# stm32f446_core.net
KiCad netlist of a schematic drawn in Altium Designer
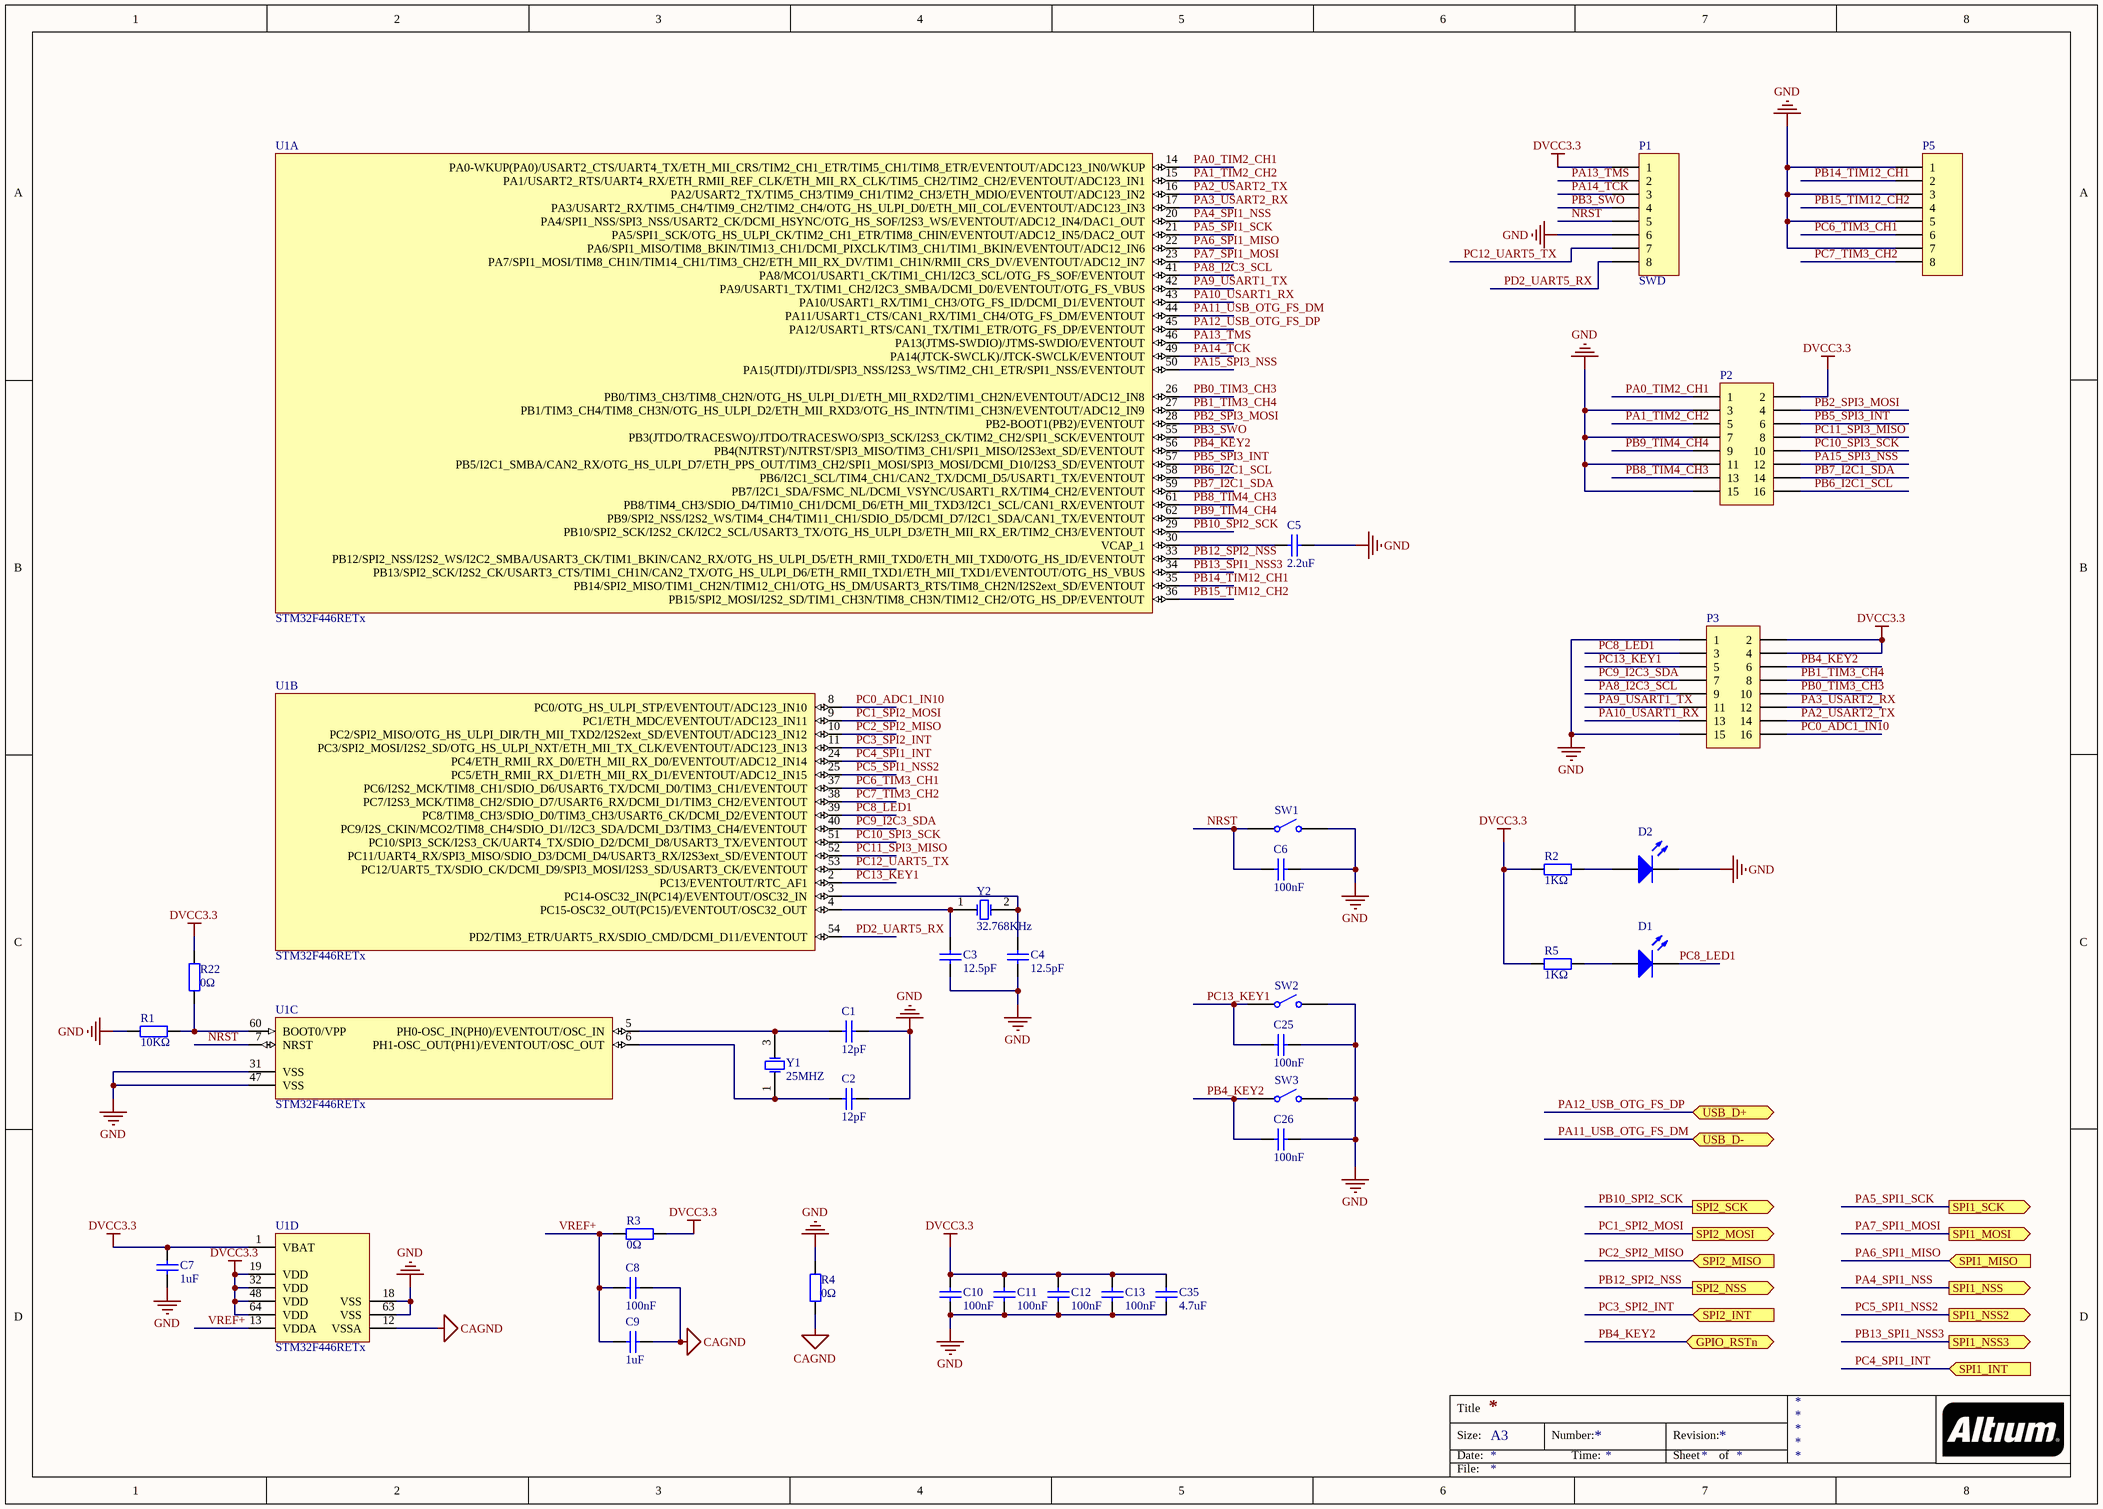
[diagram p0: stm32f446_core.SchDoc]

(export (version "E")
  (design (tool "Eeschema 10.0.6"))
  (components
    (comp (ref "C1")
      (value "12pF")
      (footprint "0603_C")
      (description "贴片电容")
      (libsource (lib "Miscellaneous Devices LC") (part "0603 12pF (120) 5% 50V"))
    )
    (comp (ref "C2")
      (value "12pF")
      (footprint "0603_C")
      (description "贴片电容")
      (libsource (lib "Miscellaneous Devices LC") (part "0603 12pF (120) 5% 50V"))
    )
    (comp (ref "C3")
      (value "12.5pF")
      (footprint "0603_C")
      (description "贴片电容")
      (libsource (lib "Miscellaneous Devices LC") (part "0603 12pF (120) 5% 50V"))
    )
    (comp (ref "C4")
      (value "12.5pF")
      (footprint "0603_C")
      (description "贴片电容")
      (libsource (lib "Miscellaneous Devices LC") (part "0603 12pF (120) 5% 50V"))
    )
    (comp (ref "C5")
      (value "2.2uF")
      (footprint "0603_C")
      (description "贴片电容")
      (libsource (lib "Miscellaneous Devices LC") (part "0603 2.2uF (225) 10% 16V"))
    )
    (comp (ref "C6")
      (value "100nF")
      (footprint "0603_C")
      (description "贴片电容")
      (libsource (lib "Miscellaneous Devices LC") (part "0603 100nF (104) 10% 50V"))
    )
    (comp (ref "C7")
      (value "1uF")
      (footprint "0603_C")
      (description "贴片电容")
      (libsource (lib "Miscellaneous Devices LC") (part "0603 1uF (105) 10% 50V"))
    )
    (comp (ref "C8")
      (value "100nF")
      (footprint "0603_C")
      (description "贴片电容")
      (libsource (lib "Miscellaneous Devices LC") (part "0603 100nF (104) 10% 50V"))
    )
    (comp (ref "C9")
      (value "1uF")
      (footprint "0603_C")
      (description "贴片电容")
      (libsource (lib "Miscellaneous Devices LC") (part "0603 1uF (105) 10% 50V"))
    )
    (comp (ref "C10")
      (value "100nF")
      (footprint "0603_C")
      (description "贴片电容")
      (libsource (lib "Miscellaneous Devices LC") (part "0603 100nF (104) 10% 50V"))
    )
    (comp (ref "C11")
      (value "100nF")
      (footprint "0603_C")
      (description "贴片电容")
      (libsource (lib "Miscellaneous Devices LC") (part "0603 100nF (104) 10% 50V"))
    )
    (comp (ref "C12")
      (value "100nF")
      (footprint "0603_C")
      (description "贴片电容")
      (libsource (lib "Miscellaneous Devices LC") (part "0603 100nF (104) 10% 50V"))
    )
    (comp (ref "C13")
      (value "100nF")
      (footprint "0603_C")
      (description "贴片电容")
      (libsource (lib "Miscellaneous Devices LC") (part "0603 100nF (104) 10% 50V"))
    )
    (comp (ref "C25")
      (value "100nF")
      (footprint "0603_C")
      (description "贴片电容")
      (libsource (lib "Miscellaneous Devices LC") (part "0603 100nF (104) 10% 50V"))
    )
    (comp (ref "C26")
      (value "100nF")
      (footprint "0603_C")
      (description "贴片电容")
      (libsource (lib "Miscellaneous Devices LC") (part "0603 100nF (104) 10% 50V"))
    )
    (comp (ref "C35")
      (value "4.7uF")
      (footprint "0603_C")
      (description "贴片电容")
      (libsource (lib "Miscellaneous Devices LC") (part "0603 4.7uF (475) 10% 16V"))
    )
    (comp (ref "D1")
      (value "蓝灯 0805")
      (footprint "0805_LED_S1")
      (description "发光二极管")
      (libsource (lib "Miscellaneous Devices LC") (part "0805 蓝灯"))
    )
    (comp (ref "D2")
      (value "蓝灯 0805")
      (footprint "0805_LED_S1")
      (description "发光二极管")
      (libsource (lib "Miscellaneous Devices LC") (part "0805 蓝灯"))
    )
    (comp (ref "P1")
      (value "SWD")
      (footprint "HDR1X8")
      (description "Header, 8-Pin")
      (fields (field (name "PUBLISHER") "Altium Limited"))
      (libsource (lib "Miscellaneous Connectors") (part "Header 8"))
    )
    (comp (ref "P2")
      (value "Header 8X2")
      (footprint "HDR2X8")
      (description "Header, 8-Pin, Dual row")
      (fields (field (name "PUBLISHER") "Altium Limited"))
      (libsource (lib "Miscellaneous Connectors") (part "Header 8X2"))
    )
    (comp (ref "P3")
      (value "Header 8X2")
      (footprint "HDR2X8")
      (description "Header, 8-Pin, Dual row")
      (fields (field (name "PUBLISHER") "Altium Limited"))
      (libsource (lib "Miscellaneous Connectors") (part "Header 8X2"))
    )
    (comp (ref "P5")
      (value "Header 8")
      (footprint "HDR1X8")
      (description "Header, 8-Pin")
      (fields (field (name "PUBLISHER") "Altium Limited"))
      (libsource (lib "Miscellaneous Connectors") (part "Header 8"))
    )
    (comp (ref "R1")
      (value "10KΩ")
      (footprint "0603_R")
      (description "贴片电阻")
      (libsource (lib "Miscellaneous Devices LC") (part "0603 10KΩ (1002) 1%"))
    )
    (comp (ref "R2")
      (value "1KΩ")
      (footprint "0603_R")
      (description "贴片电阻")
      (libsource (lib "Miscellaneous Devices LC") (part "0603 1KΩ (1001) 1%"))
    )
    (comp (ref "R3")
      (value "0Ω")
      (footprint "0603_R")
      (description "贴片电阻")
      (libsource (lib "") (part "0603 0Ω (0R0) 1%_1"))
    )
    (comp (ref "R4")
      (value "0Ω")
      (footprint "0603_R")
      (description "贴片电阻")
      (libsource (lib "Miscellaneous Devices LC") (part "0603 0Ω (0R0) 1%"))
    )
    (comp (ref "R5")
      (value "1KΩ")
      (footprint "0603_R")
      (description "贴片电阻")
      (libsource (lib "Miscellaneous Devices LC") (part "0603 1KΩ (1001) 1%"))
    )
    (comp (ref "R22")
      (value "0Ω")
      (footprint "0603_R")
      (description "贴片电阻")
      (libsource (lib "Miscellaneous Devices LC") (part "0603 0Ω (0R0) 1%"))
    )
    (comp (ref "SW1")
      (value "434111025826")
      (footprint "434111025826")
      (description "WS-TASV SMD Tact Switch 6.0X3.8 mm")
      (libsource (lib "WS-TASV SMD Tact Switch 6.0X3.5 mm") (part "434111025826"))
    )
    (comp (ref "SW2")
      (value "434111025826")
      (footprint "434111025826")
      (description "WS-TASV SMD Tact Switch 6.0X3.8 mm")
      (libsource (lib "WS-TASV SMD Tact Switch 6.0X3.5 mm") (part "434111025826"))
    )
    (comp (ref "SW3")
      (value "434111025826")
      (footprint "434111025826")
      (description "WS-TASV SMD Tact Switch 6.0X3.8 mm")
      (libsource (lib "WS-TASV SMD Tact Switch 6.0X3.5 mm") (part "434111025826"))
    )
    (comp (ref "U1")
      (value "STM32F446RETx")
      (footprint "LQFP-64_10x10x05P")
      (description "ARM")
      (libsource (lib "Miscellaneous Devices LC") (part "STM32F405RGT6"))
    )
    (comp (ref "Y1")
      (value "25MHZ")
      (footprint "SMD-3225_4P")
      (description "贴片晶振")
      (libsource (lib "Miscellaneous Devices LC") (part "SMD-3225_4P  25MHZ 12PF 10PPM"))
    )
    (comp (ref "Y2")
      (value "32.768KHz")
      (footprint "SMD-3215_2P FC - 135")
      (description "贴片晶振")
      (libsource (lib "Miscellaneous Devices LC") (part "SMD-3215_2P 32.768KHz 20ppm 12.5pF"))
    )
  )
  (nets
    (net (code "1") (name "/NRST") (class "Default")
      (node (ref "C6") (pin "1") (pinfunction "1_1") (pintype "passive"))
      (node (ref "P1") (pin "5") (pinfunction "5_5") (pintype "passive"))
      (node (ref "SW1") (pin "1") (pinfunction "1_1") (pintype "passive"))
      (node (ref "U1") (pin "7") (pinfunction "NRST_7") (pintype "bidirectional"))
    )
    (net (code "2") (name "/PA0_TIM2_CH1") (class "Default")
      (node (ref "P2") (pin "1") (pinfunction "1_1") (pintype "passive"))
      (node (ref "U1") (pin "14") (pinfunction "PA0-WKUP(PA0)/USART2_CTS/UART4_TX/ETH_MII_CRS/TIM2_CH1_ETR/TIM5_CH1/TIM8_ETR/EVENTOUT/ADC123_IN0/WKUP_14") (pintype "bidirectional"))
    )
    (net (code "3") (name "/PA1_TIM2_CH2") (class "Default")
      (node (ref "P2") (pin "5") (pinfunction "5_5") (pintype "passive"))
      (node (ref "U1") (pin "15") (pinfunction "PA1/USART2_RTS/UART4_RX/ETH_RMII_REF_CLK/ETH_MII_RX_CLK/TIM5_CH2/TIM2_CH2/EVENTOUT/ADC123_IN1_15") (pintype "bidirectional"))
    )
    (net (code "4") (name "/PA2_USART2_TX") (class "Default")
      (node (ref "P3") (pin "14") (pinfunction "14_14") (pintype "passive"))
      (node (ref "U1") (pin "16") (pinfunction "PA2/USART2_TX/TIM5_CH3/TIM9_CH1/TIM2_CH3/ETH_MDIO/EVENTOUT/ADC123_IN2_16") (pintype "bidirectional"))
    )
    (net (code "5") (name "/PA3_USART2_RX") (class "Default")
      (node (ref "P3") (pin "12") (pinfunction "12_12") (pintype "passive"))
      (node (ref "U1") (pin "17") (pinfunction "PA3/USART2_RX/TIM5_CH4/TIM9_CH2/TIM2_CH4/OTG_HS_ULPI_D0/ETH_MII_COL/EVENTOUT/ADC123_IN3_17") (pintype "bidirectional"))
    )
    (net (code "6") (name "/PA4_SPI1_NSS") (class "Default")
      (node (ref "U1") (pin "20") (pinfunction "PA4/SPI1_NSS/SPI3_NSS/USART2_CK/DCMI_HSYNC/OTG_HS_SOF/I2S3_WS/EVENTOUT/ADC12_IN4/DAC1_OUT_20") (pintype "bidirectional"))
    )
    (net (code "7") (name "/PA5_SPI1_SCK") (class "Default")
      (node (ref "U1") (pin "21") (pinfunction "PA5/SPI1_SCK/OTG_HS_ULPI_CK/TIM2_CH1_ETR/TIM8_CHIN/EVENTOUT/ADC12_IN5/DAC2_OUT_21") (pintype "bidirectional"))
    )
    (net (code "8") (name "/PA6_SPI1_MISO") (class "Default")
      (node (ref "U1") (pin "22") (pinfunction "PA6/SPI1_MISO/TIM8_BKIN/TIM13_CH1/DCMI_PIXCLK/TIM3_CH1/TIM1_BKIN/EVENTOUT/ADC12_IN6_22") (pintype "bidirectional"))
    )
    (net (code "9") (name "/PA7_SPI1_MOSI") (class "Default")
      (node (ref "U1") (pin "23") (pinfunction "PA7/SPI1_MOSI/TIM8_CH1N/TIM14_CH1/TIM3_CH2/ETH_MII_RX_DV/TIM1_CH1N/RMII_CRS_DV/EVENTOUT/ADC12_IN7_23") (pintype "bidirectional"))
    )
    (net (code "10") (name "/PA8_I2C3_SCL") (class "Default")
      (node (ref "P3") (pin "9") (pinfunction "9_9") (pintype "passive"))
      (node (ref "U1") (pin "41") (pinfunction "PA8/MCO1/USART1_CK/TIM1_CH1/I2C3_SCL/OTG_FS_SOF/EVENTOUT_41") (pintype "bidirectional"))
    )
    (net (code "11") (name "/PA9_USART1_TX") (class "Default")
      (node (ref "P3") (pin "11") (pinfunction "11_11") (pintype "passive"))
      (node (ref "U1") (pin "42") (pinfunction "PA9/USART1_TX/TIM1_CH2/I2C3_SMBA/DCMI_D0/EVENTOUT/OTG_FS_VBUS_42") (pintype "bidirectional"))
    )
    (net (code "12") (name "/PA10_USART1_RX") (class "Default")
      (node (ref "P3") (pin "13") (pinfunction "13_13") (pintype "passive"))
      (node (ref "U1") (pin "43") (pinfunction "PA10/USART1_RX/TIM1_CH3/OTG_FS_ID/DCMI_D1/EVENTOUT_43") (pintype "bidirectional"))
    )
    (net (code "13") (name "/PA11_USB_OTG_FS_DM") (class "Default")
      (node (ref "U1") (pin "44") (pinfunction "PA11/USART1_CTS/CAN1_RX/TIM1_CH4/OTG_FS_DM/EVENTOUT_44") (pintype "bidirectional"))
    )
    (net (code "14") (name "/PA12_USB_OTG_FS_DP") (class "Default")
      (node (ref "U1") (pin "45") (pinfunction "PA12/USART1_RTS/CAN1_TX/TIM1_ETR/OTG_FS_DP/EVENTOUT_45") (pintype "bidirectional"))
    )
    (net (code "15") (name "/PA13_TMS") (class "Default")
      (node (ref "P1") (pin "2") (pinfunction "2_2") (pintype "passive"))
      (node (ref "U1") (pin "46") (pinfunction "PA13(JTMS-SWDIO)/JTMS-SWDIO/EVENTOUT_46") (pintype "bidirectional"))
    )
    (net (code "16") (name "/PA14_TCK") (class "Default")
      (node (ref "P1") (pin "3") (pinfunction "3_3") (pintype "passive"))
      (node (ref "U1") (pin "49") (pinfunction "PA14(JTCK-SWCLK)/JTCK-SWCLK/EVENTOUT_49") (pintype "bidirectional"))
    )
    (net (code "17") (name "/PA15_SPI3_NSS") (class "Default")
      (node (ref "P2") (pin "12") (pinfunction "12_12") (pintype "passive"))
      (node (ref "U1") (pin "50") (pinfunction "PA15(JTDI)/JTDI/SPI3_NSS/I2S3_WS/TIM2_CH1_ETR/SPI1_NSS/EVENTOUT_50") (pintype "bidirectional"))
    )
    (net (code "18") (name "/PB0_TIM3_CH3") (class "Default")
      (node (ref "P3") (pin "10") (pinfunction "10_10") (pintype "passive"))
      (node (ref "U1") (pin "26") (pinfunction "PB0/TIM3_CH3/TIM8_CH2N/OTG_HS_ULPI_D1/ETH_MII_RXD2/TIM1_CH2N/EVENTOUT/ADC12_IN8_26") (pintype "bidirectional"))
    )
    (net (code "19") (name "/PB1_TIM3_CH4") (class "Default")
      (node (ref "P3") (pin "8") (pinfunction "8_8") (pintype "passive"))
      (node (ref "U1") (pin "27") (pinfunction "PB1/TIM3_CH4/TIM8_CH3N/OTG_HS_ULPI_D2/ETH_MII_RXD3/OTG_HS_INTN/TIM1_CH3N/EVENTOUT/ADC12_IN9_27") (pintype "bidirectional"))
    )
    (net (code "20") (name "/PB2_SPI3_MOSI") (class "Default")
      (node (ref "P2") (pin "4") (pinfunction "4_4") (pintype "passive"))
      (node (ref "U1") (pin "28") (pinfunction "PB2-BOOT1(PB2)/EVENTOUT_28") (pintype "bidirectional"))
    )
    (net (code "21") (name "/PB3_SWO") (class "Default")
      (node (ref "P1") (pin "4") (pinfunction "4_4") (pintype "passive"))
      (node (ref "U1") (pin "55") (pinfunction "PB3(JTDO/TRACESWO)/JTDO/TRACESWO/SPI3_SCK/I2S3_CK/TIM2_CH2/SPI1_SCK/EVENTOUT_55") (pintype "bidirectional"))
    )
    (net (code "22") (name "/PB4_KEY2") (class "Default")
      (node (ref "C26") (pin "1") (pinfunction "1_1") (pintype "passive"))
      (node (ref "P3") (pin "6") (pinfunction "6_6") (pintype "passive"))
      (node (ref "SW3") (pin "1") (pinfunction "1_1") (pintype "passive"))
      (node (ref "U1") (pin "56") (pinfunction "PB4(NJTRST)/NJTRST/SPI3_MISO/TIM3_CH1/SPI1_MISO/I2S3ext_SD/EVENTOUT_56") (pintype "bidirectional"))
    )
    (net (code "23") (name "/PB5_SPI3_INT") (class "Default")
      (node (ref "P2") (pin "6") (pinfunction "6_6") (pintype "passive"))
      (node (ref "U1") (pin "57") (pinfunction "PB5/I2C1_SMBA/CAN2_RX/OTG_HS_ULPI_D7/ETH_PPS_OUT/TIM3_CH2/SPI1_MOSI/SPI3_MOSI/DCMI_D10/I2S3_SD/EVENTOUT_57") (pintype "bidirectional"))
    )
    (net (code "24") (name "/PB6_I2C1_SCL") (class "Default")
      (node (ref "P2") (pin "16") (pinfunction "16_16") (pintype "passive"))
      (node (ref "U1") (pin "58") (pinfunction "PB6/I2C1_SCL/TIM4_CH1/CAN2_TX/DCMI_D5/USART1_TX/EVENTOUT_58") (pintype "bidirectional"))
    )
    (net (code "25") (name "/PB7_I2C1_SDA") (class "Default")
      (node (ref "P2") (pin "14") (pinfunction "14_14") (pintype "passive"))
      (node (ref "U1") (pin "59") (pinfunction "PB7/I2C1_SDA/FSMC_NL/DCMI_VSYNC/USART1_RX/TIM4_CH2/EVENTOUT_59") (pintype "bidirectional"))
    )
    (net (code "26") (name "/PB8_TIM4_CH3") (class "Default")
      (node (ref "P2") (pin "13") (pinfunction "13_13") (pintype "passive"))
      (node (ref "U1") (pin "61") (pinfunction "PB8/TIM4_CH3/SDIO_D4/TIM10_CH1/DCMI_D6/ETH_MII_TXD3/I2C1_SCL/CAN1_RX/EVENTOUT_61") (pintype "bidirectional"))
    )
    (net (code "27") (name "/PB9_TIM4_CH4") (class "Default")
      (node (ref "P2") (pin "9") (pinfunction "9_9") (pintype "passive"))
      (node (ref "U1") (pin "62") (pinfunction "PB9/SPI2_NSS/I2S2_WS/TIM4_CH4/TIM11_CH1/SDIO_D5/DCMI_D7/I2C1_SDA/CAN1_TX/EVENTOUT_62") (pintype "bidirectional"))
    )
    (net (code "28") (name "/PB10_SPI2_SCK") (class "Default")
      (node (ref "U1") (pin "29") (pinfunction "PB10/SPI2_SCK/I2S2_CK/I2C2_SCL/USART3_TX/OTG_HS_ULPI_D3/ETH_MII_RX_ER/TIM2_CH3/EVENTOUT_29") (pintype "bidirectional"))
    )
    (net (code "29") (name "/PB12_SPI2_NSS") (class "Default")
      (node (ref "U1") (pin "33") (pinfunction "PB12/SPI2_NSS/I2S2_WS/I2C2_SMBA/USART3_CK/TIM1_BKIN/CAN2_RX/OTG_HS_ULPI_D5/ETH_RMII_TXD0/ETH_MII_TXD0/OTG_HS_ID/EVENTOUT_33") (pintype "bidirectional"))
    )
    (net (code "30") (name "/PB13_SPI1_NSS3") (class "Default")
      (node (ref "U1") (pin "34") (pinfunction "PB13/SPI2_SCK/I2S2_CK/USART3_CTS/TIM1_CH1N/CAN2_TX/OTG_HS_ULPI_D6/ETH_RMII_TXD1/ETH_MII_TXD1/EVENTOUT/OTG_HS_VBUS_34") (pintype "bidirectional"))
    )
    (net (code "31") (name "/PB14_TIM12_CH1") (class "Default")
      (node (ref "P5") (pin "2") (pinfunction "2_2") (pintype "passive"))
      (node (ref "U1") (pin "35") (pinfunction "PB14/SPI2_MISO/TIM1_CH2N/TIM12_CH1/OTG_HS_DM/USART3_RTS/TIM8_CH2N/I2S2ext_SD/EVENTOUT_35") (pintype "bidirectional"))
    )
    (net (code "32") (name "/PB15_TIM12_CH2") (class "Default")
      (node (ref "P5") (pin "4") (pinfunction "4_4") (pintype "passive"))
      (node (ref "U1") (pin "36") (pinfunction "PB15/SPI2_MOSI/I2S2_SD/TIM1_CH3N/TIM8_CH3N/TIM12_CH2/OTG_HS_DP/EVENTOUT_36") (pintype "bidirectional"))
    )
    (net (code "33") (name "/PC0_ADC1_IN10") (class "Default")
      (node (ref "P3") (pin "16") (pinfunction "16_16") (pintype "passive"))
      (node (ref "U1") (pin "8") (pinfunction "PC0/OTG_HS_ULPI_STP/EVENTOUT/ADC123_IN10_8") (pintype "bidirectional"))
    )
    (net (code "34") (name "/PC1_SPI2_MOSI") (class "Default")
      (node (ref "U1") (pin "9") (pinfunction "PC1/ETH_MDC/EVENTOUT/ADC123_IN11_9") (pintype "bidirectional"))
    )
    (net (code "35") (name "/PC2_SPI2_MISO") (class "Default")
      (node (ref "U1") (pin "10") (pinfunction "PC2/SPI2_MISO/OTG_HS_ULPI_DIR/TH_MII_TXD2/I2S2ext_SD/EVENTOUT/ADC123_IN12_10") (pintype "bidirectional"))
    )
    (net (code "36") (name "/PC3_SPI2_INT") (class "Default")
      (node (ref "U1") (pin "11") (pinfunction "PC3/SPI2_MOSI/I2S2_SD/OTG_HS_ULPI_NXT/ETH_MII_TX_CLK/EVENTOUT/ADC123_IN13_11") (pintype "bidirectional"))
    )
    (net (code "37") (name "/PC4_SPI1_INT") (class "Default")
      (node (ref "U1") (pin "24") (pinfunction "PC4/ETH_RMII_RX_D0/ETH_MII_RX_D0/EVENTOUT/ADC12_IN14_24") (pintype "bidirectional"))
    )
    (net (code "38") (name "/PC5_SPI1_NSS2") (class "Default")
      (node (ref "U1") (pin "25") (pinfunction "PC5/ETH_RMII_RX_D1/ETH_MII_RX_D1/EVENTOUT/ADC12_IN15_25") (pintype "bidirectional"))
    )
    (net (code "39") (name "/PC6_TIM3_CH1") (class "Default")
      (node (ref "P5") (pin "6") (pinfunction "6_6") (pintype "passive"))
      (node (ref "U1") (pin "37") (pinfunction "PC6/I2S2_MCK/TIM8_CH1/SDIO_D6/USART6_TX/DCMI_D0/TIM3_CH1/EVENTOUT_37") (pintype "bidirectional"))
    )
    (net (code "40") (name "/PC7_TIM3_CH2") (class "Default")
      (node (ref "P5") (pin "8") (pinfunction "8_8") (pintype "passive"))
      (node (ref "U1") (pin "38") (pinfunction "PC7/I2S3_MCK/TIM8_CH2/SDIO_D7/USART6_RX/DCMI_D1/TIM3_CH2/EVENTOUT_38") (pintype "bidirectional"))
    )
    (net (code "41") (name "/PC8_LED1") (class "Default")
      (node (ref "D1") (pin "K") (pinfunction "K_K") (pintype "passive"))
      (node (ref "P3") (pin "3") (pinfunction "3_3") (pintype "passive"))
      (node (ref "U1") (pin "39") (pinfunction "PC8/TIM8_CH3/SDIO_D0/TIM3_CH3/USART6_CK/DCMI_D2/EVENTOUT_39") (pintype "bidirectional"))
    )
    (net (code "42") (name "/PC9_I2C3_SDA") (class "Default")
      (node (ref "P3") (pin "7") (pinfunction "7_7") (pintype "passive"))
      (node (ref "U1") (pin "40") (pinfunction "PC9/I2S_CKIN/MCO2/TIM8_CH4/SDIO_D1//I2C3_SDA/DCMI_D3/TIM3_CH4/EVENTOUT_40") (pintype "bidirectional"))
    )
    (net (code "43") (name "/PC10_SPI3_SCK") (class "Default")
      (node (ref "P2") (pin "10") (pinfunction "10_10") (pintype "passive"))
      (node (ref "U1") (pin "51") (pinfunction "PC10/SPI3_SCK/I2S3_CK/UART4_TX/SDIO_D2/DCMI_D8/USART3_TX/EVENTOUT_51") (pintype "bidirectional"))
    )
    (net (code "44") (name "/PC11_SPI3_MISO") (class "Default")
      (node (ref "P2") (pin "8") (pinfunction "8_8") (pintype "passive"))
      (node (ref "U1") (pin "52") (pinfunction "PC11/UART4_RX/SPI3_MISO/SDIO_D3/DCMI_D4/USART3_RX/I2S3ext_SD/EVENTOUT_52") (pintype "bidirectional"))
    )
    (net (code "45") (name "/PC12_UART5_TX") (class "Default")
      (node (ref "P1") (pin "7") (pinfunction "7_7") (pintype "passive"))
      (node (ref "U1") (pin "53") (pinfunction "PC12/UART5_TX/SDIO_CK/DCMI_D9/SPI3_MOSI/I2S3_SD/USART3_CK/EVENTOUT_53") (pintype "bidirectional"))
    )
    (net (code "46") (name "/PC13_KEY1") (class "Default")
      (node (ref "C25") (pin "1") (pinfunction "1_1") (pintype "passive"))
      (node (ref "P3") (pin "5") (pinfunction "5_5") (pintype "passive"))
      (node (ref "SW2") (pin "1") (pinfunction "1_1") (pintype "passive"))
      (node (ref "U1") (pin "2") (pinfunction "PC13/EVENTOUT/RTC_AF1_2") (pintype "bidirectional"))
    )
    (net (code "47") (name "/PD2_UART5_RX") (class "Default")
      (node (ref "P1") (pin "8") (pinfunction "8_8") (pintype "passive"))
      (node (ref "U1") (pin "54") (pinfunction "PD2/TIM3_ETR/UART5_RX/SDIO_CMD/DCMI_D11/EVENTOUT_54") (pintype "bidirectional"))
    )
    (net (code "48") (name "/VREF+") (class "Default")
      (node (ref "C8") (pin "1") (pinfunction "1_1") (pintype "passive"))
      (node (ref "C9") (pin "1") (pinfunction "1_1") (pintype "passive"))
      (node (ref "R3") (pin "1") (pinfunction "1_1") (pintype "passive"))
      (node (ref "U1") (pin "13") (pinfunction "VDDA_13") (pintype "power_in"))
    )
    (net (code "49") (name "CAGND") (class "Default")
      (node (ref "C8") (pin "2") (pinfunction "2_2") (pintype "passive"))
      (node (ref "C9") (pin "2") (pinfunction "2_2") (pintype "passive"))
      (node (ref "R4") (pin "1") (pinfunction "1_1") (pintype "passive"))
      (node (ref "U1") (pin "12") (pinfunction "VSSA_12") (pintype "power_in"))
    )
    (net (code "50") (name "DVCC3.3") (class "Default")
      (node (ref "C10") (pin "2") (pinfunction "2_2") (pintype "passive"))
      (node (ref "C11") (pin "2") (pinfunction "2_2") (pintype "passive"))
      (node (ref "C12") (pin "2") (pinfunction "2_2") (pintype "passive"))
      (node (ref "C13") (pin "1") (pinfunction "1_1") (pintype "passive"))
      (node (ref "C35") (pin "2") (pinfunction "2_2") (pintype "passive"))
      (node (ref "C7") (pin "2") (pinfunction "2_2") (pintype "passive"))
      (node (ref "P1") (pin "1") (pinfunction "1_1") (pintype "passive"))
      (node (ref "P2") (pin "2") (pinfunction "2_2") (pintype "passive"))
      (node (ref "P3") (pin "2") (pinfunction "2_2") (pintype "passive"))
      (node (ref "P3") (pin "4") (pinfunction "4_4") (pintype "passive"))
      (node (ref "R2") (pin "1") (pinfunction "1_1") (pintype "passive"))
      (node (ref "R22") (pin "2") (pinfunction "2_2") (pintype "passive"))
      (node (ref "R3") (pin "2") (pinfunction "2_2") (pintype "passive"))
      (node (ref "R5") (pin "1") (pinfunction "1_1") (pintype "passive"))
      (node (ref "U1") (pin "1") (pinfunction "VBAT_1") (pintype "power_in"))
      (node (ref "U1") (pin "19") (pinfunction "VDD_19") (pintype "power_in"))
      (node (ref "U1") (pin "32") (pinfunction "VDD_32") (pintype "power_in"))
      (node (ref "U1") (pin "48") (pinfunction "VDD_48") (pintype "power_in"))
      (node (ref "U1") (pin "64") (pinfunction "VDD_64") (pintype "power_in"))
    )
    (net (code "51") (name "GND") (class "Default")
      (node (ref "C1") (pin "2") (pinfunction "2_2") (pintype "passive"))
      (node (ref "C10") (pin "1") (pinfunction "1_1") (pintype "passive"))
      (node (ref "C11") (pin "1") (pinfunction "1_1") (pintype "passive"))
      (node (ref "C12") (pin "1") (pinfunction "1_1") (pintype "passive"))
      (node (ref "C13") (pin "2") (pinfunction "2_2") (pintype "passive"))
      (node (ref "C2") (pin "2") (pinfunction "2_2") (pintype "passive"))
      (node (ref "C25") (pin "2") (pinfunction "2_2") (pintype "passive"))
      (node (ref "C26") (pin "2") (pinfunction "2_2") (pintype "passive"))
      (node (ref "C3") (pin "1") (pinfunction "1_1") (pintype "passive"))
      (node (ref "C35") (pin "1") (pinfunction "1_1") (pintype "passive"))
      (node (ref "C4") (pin "1") (pinfunction "1_1") (pintype "passive"))
      (node (ref "C5") (pin "1") (pinfunction "1_1") (pintype "passive"))
      (node (ref "C6") (pin "2") (pinfunction "2_2") (pintype "passive"))
      (node (ref "C7") (pin "1") (pinfunction "1_1") (pintype "passive"))
      (node (ref "D2") (pin "K") (pinfunction "K_K") (pintype "passive"))
      (node (ref "P1") (pin "6") (pinfunction "6_6") (pintype "passive"))
      (node (ref "P2") (pin "11") (pinfunction "11_11") (pintype "passive"))
      (node (ref "P2") (pin "15") (pinfunction "15_15") (pintype "passive"))
      (node (ref "P2") (pin "3") (pinfunction "3_3") (pintype "passive"))
      (node (ref "P2") (pin "7") (pinfunction "7_7") (pintype "passive"))
      (node (ref "P3") (pin "1") (pinfunction "1_1") (pintype "passive"))
      (node (ref "P3") (pin "15") (pinfunction "15_15") (pintype "passive"))
      (node (ref "P5") (pin "1") (pinfunction "1_1") (pintype "passive"))
      (node (ref "P5") (pin "3") (pinfunction "3_3") (pintype "passive"))
      (node (ref "P5") (pin "5") (pinfunction "5_5") (pintype "passive"))
      (node (ref "P5") (pin "7") (pinfunction "7_7") (pintype "passive"))
      (node (ref "R1") (pin "1") (pinfunction "1_1") (pintype "passive"))
      (node (ref "R4") (pin "2") (pinfunction "2_2") (pintype "passive"))
      (node (ref "SW1") (pin "2") (pinfunction "2_2") (pintype "passive"))
      (node (ref "SW2") (pin "2") (pinfunction "2_2") (pintype "passive"))
      (node (ref "SW3") (pin "2") (pinfunction "2_2") (pintype "passive"))
      (node (ref "U1") (pin "18") (pinfunction "VSS_18") (pintype "power_in"))
      (node (ref "U1") (pin "31") (pinfunction "VCAP_1_31") (pintype "power_in"))
      (node (ref "U1") (pin "47") (pinfunction "VCAP_2_47") (pintype "power_in"))
      (node (ref "U1") (pin "63") (pinfunction "VSS_63") (pintype "power_in"))
    )
    (net (code "52") (name "Net-(D1-PadA)") (class "Default")
      (node (ref "D1") (pin "A") (pinfunction "A_A") (pintype "passive"))
      (node (ref "R5") (pin "2") (pinfunction "2_2") (pintype "passive"))
    )
    (net (code "53") (name "Net-(D2-PadA)") (class "Default")
      (node (ref "D2") (pin "A") (pinfunction "A_A") (pintype "passive"))
      (node (ref "R2") (pin "2") (pinfunction "2_2") (pintype "passive"))
    )
    (net (code "54") (name "Net-(U1A-PB11{slash}I2C2_SDA{slash}USART3_RX{slash}OTG_HS_ULPI_D4{slash}ETH_RMII_TX_EN{slash}ETH_MII_TX_EN{slash}TIM2_CH4{slash}EVENTOUT)") (class "Default")
      (node (ref "C5") (pin "2") (pinfunction "2_2") (pintype "passive"))
      (node (ref "U1") (pin "30") (pinfunction "PB11/I2C2_SDA/USART3_RX/OTG_HS_ULPI_D4/ETH_RMII_TX_EN/ETH_MII_TX_EN/TIM2_CH4/EVENTOUT_30") (pintype "bidirectional"))
    )
    (net (code "55") (name "Net-(U1B-PC14-OSC32_IN(PC14){slash}EVENTOUT{slash}OSC32_IN)") (class "Default")
      (node (ref "C4") (pin "2") (pinfunction "2_2") (pintype "passive"))
      (node (ref "U1") (pin "3") (pinfunction "PC14-OSC32_IN(PC14)/EVENTOUT/OSC32_IN_3") (pintype "bidirectional"))
      (node (ref "Y2") (pin "2") (pinfunction "OSC2_2") (pintype "passive"))
    )
    (net (code "56") (name "Net-(U1B-PC15-OSC32_OUT(PC15){slash}EVENTOUT{slash}OSC32_OUT)") (class "Default")
      (node (ref "C3") (pin "2") (pinfunction "2_2") (pintype "passive"))
      (node (ref "U1") (pin "4") (pinfunction "PC15-OSC32_OUT(PC15)/EVENTOUT/OSC32_OUT_4") (pintype "bidirectional"))
      (node (ref "Y2") (pin "1") (pinfunction "OSC1_1") (pintype "passive"))
    )
    (net (code "57") (name "Net-(U1C-BOOT0{slash}VPP)") (class "Default")
      (node (ref "R1") (pin "2") (pinfunction "2_2") (pintype "passive"))
      (node (ref "R22") (pin "1") (pinfunction "1_1") (pintype "passive"))
      (node (ref "U1") (pin "60") (pinfunction "BOOT0/VPP_60") (pintype "input"))
    )
    (net (code "58") (name "Net-(U1C-PH0-OSC_IN(PH0){slash}EVENTOUT{slash}OSC_IN)") (class "Default")
      (node (ref "C1") (pin "1") (pinfunction "1_1") (pintype "passive"))
      (node (ref "U1") (pin "5") (pinfunction "PH0-OSC_IN(PH0)/EVENTOUT/OSC_IN_5") (pintype "bidirectional"))
      (node (ref "Y1") (pin "3") (pinfunction "OSC2_3") (pintype "passive"))
    )
    (net (code "59") (name "Net-(U1C-PH1-OSC_OUT(PH1){slash}EVENTOUT{slash}OSC_OUT)") (class "Default")
      (node (ref "C2") (pin "1") (pinfunction "1_1") (pintype "passive"))
      (node (ref "U1") (pin "6") (pinfunction "PH1-OSC_OUT(PH1)/EVENTOUT/OSC_OUT_6") (pintype "bidirectional"))
      (node (ref "Y1") (pin "1") (pinfunction "OSC1_1") (pintype "passive"))
    )
  )
)
